# SHEET1.net
KiCad netlist of a schematic drawn in Altium Designer
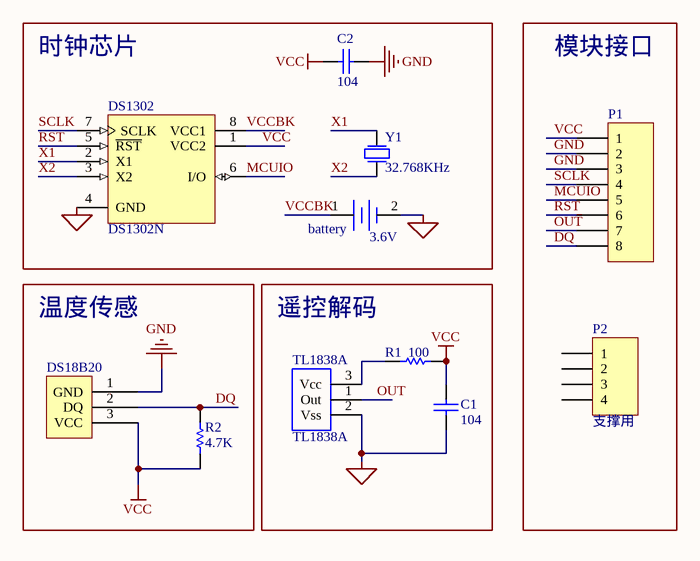
[diagram p0: SHEET1.SCHDOC]

(export (version "E")
  (design (tool "Eeschema 10.0.6"))
  (components
    (comp (ref "battery") (value "3.6V") (footprint "POW1_HT") (libsource (lib "Schlib1") (part "BATTERY")))
    (comp (ref "C1")
      (value "CAP")
      (footprint "CAP2A_DQ")
      (description "CAP with C0805 footprint")
      (fields (field (name "ALTIUM_UNNAMED_1") "104"))
      (libsource (lib "MyLib") (part "CAP0805"))
    )
    (comp (ref "C2")
      (value "CAP")
      (footprint "CAP2A_DQ")
      (description "CAP with C0805 footprint")
      (fields (field (name "ALTIUM_UNNAMED_1") "104"))
      (libsource (lib "MyLib") (part "CAP0805"))
    )
    (comp (ref "DS18B20") (value "DALLAS IC") (footprint "TO92C") (libsource (lib "MyLib") (part "DS18B20")))
    (comp (ref "DS1302")
      (value "DS1302N")
      (footprint "DIP8")
      (description "Trickle Charge Timekeeping Chip")
      (fields (field (name "PUBLISHER") "Altium Limited"))
      (libsource (lib "Dallas Peripheral Real Time Clock") (part "DS1302N"))
    )
    (comp (ref "P1")
      (value "Header 8")
      (footprint "HDR1X8")
      (description "Header, 8-Pin")
      (fields (field (name "PUBLISHER") "Altium Limited"))
      (libsource (lib "Miscellaneous Connectors") (part "Header 8"))
    )
    (comp (ref "P2")
      (value "支撑用")
      (footprint "HDR1X4")
      (description "支撑作用")
      (fields (field (name "PUBLISHER") "Altium Limited"))
      (libsource (lib "Miscellaneous Connectors") (part "Header 4"))
    )
    (comp (ref "R1")
      (value "Resister")
      (footprint "AXIAL-0.3")
      (description "Resister with c0805 footprint")
      (fields (field (name "ALTIUM_UNNAMED_1") "100"))
      (libsource (lib "MyLib") (part "Resister"))
    )
    (comp (ref "R2")
      (value "Resister")
      (footprint "AXIAL-0.3")
      (description "Resister with c0805 footprint")
      (fields (field (name "ALTIUM_UNNAMED_1") "4.7K"))
      (libsource (lib "MyLib") (part "Resister"))
    )
    (comp (ref "TL1838A")
      (value "TL1838A")
      (footprint "DIP3_HT")
      (libsource (lib "Schlib1") (part "TL1838A"))
    )
    (comp (ref "Y1")
      (value "32.768KHz")
      (footprint "BCY-W2/D3.1")
      (description "Crystal Oscillator")
      (libsource (lib "*") (part "12MHZ"))
    )
  )
  (nets
    (net (code "1") (name "/DQ") (class "Default")
      (node (ref "DS18B20") (pin "2") (pinfunction "DQ_2") (pintype "passive"))
      (node (ref "P1") (pin "8") (pinfunction "8_8") (pintype "passive"))
      (node (ref "R2") (pin "1") (pinfunction "1_1") (pintype "passive"))
    )
    (net (code "2") (name "/MCUIO") (class "Default")
      (node (ref "DS1302") (pin "6") (pinfunction "I/O_6") (pintype "bidirectional"))
      (node (ref "P1") (pin "5") (pinfunction "5_5") (pintype "passive"))
    )
    (net (code "3") (name "/OUT") (class "Default")
      (node (ref "P1") (pin "7") (pinfunction "7_7") (pintype "passive"))
      (node (ref "TL1838A") (pin "1") (pinfunction "Out_1") (pintype "passive"))
    )
    (net (code "4") (name "/RST") (class "Default")
      (node (ref "DS1302") (pin "5") (pinfunction "~{RST}_5") (pintype "input"))
      (node (ref "P1") (pin "6") (pinfunction "6_6") (pintype "passive"))
    )
    (net (code "5") (name "/SCLK") (class "Default")
      (node (ref "DS1302") (pin "7") (pinfunction "SCLK_7") (pintype "input"))
      (node (ref "P1") (pin "4") (pinfunction "4_4") (pintype "passive"))
    )
    (net (code "6") (name "/VCCBK") (class "Default")
      (node (ref "DS1302") (pin "8") (pinfunction "VCC1_8") (pintype "power_in"))
      (node (ref "battery") (pin "1") (pinfunction "+_1") (pintype "passive"))
    )
    (net (code "7") (name "/X1") (class "Default")
      (node (ref "DS1302") (pin "2") (pinfunction "X1_2") (pintype "input"))
      (node (ref "Y1") (pin "1") (pinfunction "P1_1") (pintype "passive"))
    )
    (net (code "8") (name "/X2") (class "Default")
      (node (ref "DS1302") (pin "3") (pinfunction "X2_3") (pintype "input"))
      (node (ref "Y1") (pin "2") (pinfunction "P2_2") (pintype "passive"))
    )
    (net (code "9") (name "GND") (class "Default")
      (node (ref "C1") (pin "2") (pinfunction "2_2") (pintype "passive"))
      (node (ref "C2") (pin "2") (pinfunction "2_2") (pintype "passive"))
      (node (ref "DS1302") (pin "4") (pinfunction "GND_4") (pintype "power_in"))
      (node (ref "DS18B20") (pin "1") (pinfunction "GND_1") (pintype "passive"))
      (node (ref "P1") (pin "2") (pinfunction "2_2") (pintype "passive"))
      (node (ref "P1") (pin "3") (pinfunction "3_3") (pintype "passive"))
      (node (ref "TL1838A") (pin "2") (pinfunction "Vss_2") (pintype "passive"))
      (node (ref "battery") (pin "2") (pinfunction "-_2") (pintype "passive"))
    )
    (net (code "10") (name "Net-(TL1838A-Vcc)") (class "Default")
      (node (ref "R1") (pin "2") (pinfunction "2_2") (pintype "passive"))
      (node (ref "TL1838A") (pin "3") (pinfunction "Vcc_3") (pintype "passive"))
    )
    (net (code "11") (name "VCC") (class "Default")
      (node (ref "C1") (pin "1") (pinfunction "1_1") (pintype "passive"))
      (node (ref "C2") (pin "1") (pinfunction "1_1") (pintype "passive"))
      (node (ref "DS1302") (pin "1") (pinfunction "VCC2_1") (pintype "power_in"))
      (node (ref "DS18B20") (pin "3") (pinfunction "VCC_3") (pintype "passive"))
      (node (ref "P1") (pin "1") (pinfunction "1_1") (pintype "passive"))
      (node (ref "R1") (pin "1") (pinfunction "1_1") (pintype "passive"))
      (node (ref "R2") (pin "2") (pinfunction "2_2") (pintype "passive"))
    )
    (net (code "12") (name "unconnected-(P2-Pad1)") (class "Default")
      (node (ref "P2") (pin "1") (pinfunction "1_1") (pintype "passive"))
    )
    (net (code "13") (name "unconnected-(P2-Pad2)") (class "Default")
      (node (ref "P2") (pin "2") (pinfunction "2_2") (pintype "passive"))
    )
    (net (code "14") (name "unconnected-(P2-Pad3)") (class "Default")
      (node (ref "P2") (pin "3") (pinfunction "3_3") (pintype "passive"))
    )
    (net (code "15") (name "unconnected-(P2-Pad4)") (class "Default")
      (node (ref "P2") (pin "4") (pinfunction "4_4") (pintype "passive"))
    )
  )
)
